# Main.net
KiCad netlist of a schematic drawn in Altium Designer
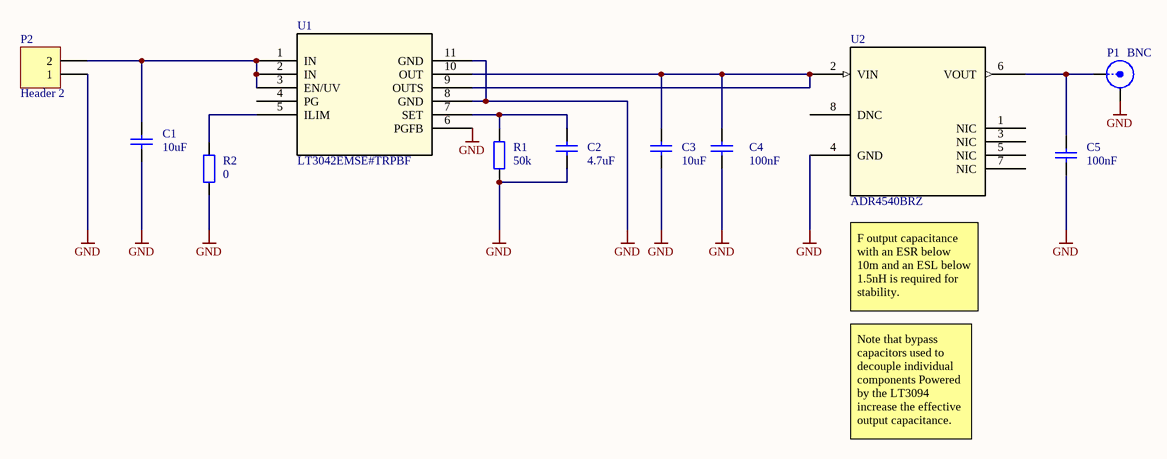
[diagram p0: Main.SchDoc]

(export (version "E")
  (design (tool "Eeschema 10.0.6"))
  (components
    (comp (ref "C1")
      (value "10uF")
      (footprint "C1206-KUE")
      (description "Capacitor")
      (fields (field (name "MANUFACTURER") "Kemet") (field (name "PUBLISHER") "Altium Limited"))
      (libsource (lib "ExtrapartsKUE_V01") (part "Capacitor"))
    )
    (comp (ref "C2")
      (value "4.7uF")
      (footprint "C1206-KUE")
      (description "Capacitor X7R")
      (fields (field (name "MANUFACTURER") "Kemet") (field (name "PUBLISHER") "Altium Limited"))
      (libsource (lib "ExtrapartsKUE_V01") (part "Capacitor"))
    )
    (comp (ref "C3")
      (value "10uF")
      (footprint "C1206-KUE")
      (description "Capacitor X7R")
      (fields (field (name "MANUFACTURER") "Kemet") (field (name "PUBLISHER") "Altium Limited"))
      (libsource (lib "ExtrapartsKUE_V01") (part "Capacitor"))
    )
    (comp (ref "C4")
      (value "100nF")
      (footprint "C1206-KUE")
      (description "Capacitor X7R")
      (fields (field (name "MANUFACTURER") "Kemet") (field (name "PUBLISHER") "Altium Limited"))
      (libsource (lib "ExtrapartsKUE_V01") (part "Capacitor"))
    )
    (comp (ref "C5")
      (value "100nF")
      (footprint "C1206-KUE")
      (description "Capacitor X7r")
      (fields (field (name "MANUFACTURER") "Kemet") (field (name "PUBLISHER") "Altium Limited"))
      (libsource (lib "ExtrapartsKUE_V01") (part "Capacitor"))
    )
    (comp (ref "P1")
      (value "BNC")
      (footprint "BNC_RA CON")
      (description "BNC Elbow Connector")
      (fields (field (name "PUBLISHER") "Altium Limited"))
      (libsource (lib "Miscellaneous Connectors") (part "BNC"))
    )
    (comp (ref "P2")
      (value "Header 2")
      (footprint "HDR1X2")
      (description "Header, 2-Pin")
      (fields (field (name "PUBLISHER") "Altium Limited"))
      (libsource (lib "Miscellaneous Connectors") (part "Header 2"))
    )
    (comp (ref "R1")
      (value "50k")
      (footprint "C1206-KUE")
      (description "Resistor SMD 1%")
      (fields (field (name "MANUFACTURER") "AVX") (field (name "PUBLISHER") "Altium Limited"))
      (libsource (lib "ExtrapartsKUE_V01") (part "ResistorSMD"))
    )
    (comp (ref "R2")
      (value "0")
      (footprint "C1206-KUE")
      (description "Resistor SMD")
      (fields (field (name "MANUFACTURER") "AVX") (field (name "PUBLISHER") "Altium Limited"))
      (libsource (lib "ExtrapartsKUE_V01") (part "ResistorSMD"))
    )
    (comp (ref "U1")
      (value "LT3042EMSE#TRPBF")
      (footprint "05-08-1664_ADI")
      (description "20V, 200mA, Ultralow Noise, Ultrahigh PSRR RF Linear Regulator")
      (fields (field (name "COPYRIGHT") "Copyright (C) 2025 Ultra Librarian. All rights reserved."))
      (libsource (lib "MyOwnParts") (part "LT3042EMSETRPBF"))
    )
    (comp (ref "U2")
      (value "ADR4540BRZ")
      (footprint "R-8_ADI")
      (description "Ultra-Low-Noise, High-Accuracy 4.096V Voltage Reference")
      (fields (field (name "COPYRIGHT") "Copyright (C) 2025 Ultra Librarian. All rights reserved."))
      (libsource (lib "ADR4540BRZ") (part "ADR4540BRZ"))
    )
  )
  (nets
    (net (code "1") (name "GND") (class "Default")
      (node (ref "C1") (pin "1") (pinfunction "1_1") (pintype "passive"))
      (node (ref "C2") (pin "1") (pinfunction "1_1") (pintype "passive"))
      (node (ref "C3") (pin "1") (pinfunction "1_1") (pintype "passive"))
      (node (ref "C4") (pin "1") (pinfunction "1_1") (pintype "passive"))
      (node (ref "C5") (pin "1") (pinfunction "1_1") (pintype "passive"))
      (node (ref "P1") (pin "2") (pinfunction "Y_2") (pintype "passive"))
      (node (ref "P2") (pin "1") (pinfunction "1_1") (pintype "passive"))
      (node (ref "R1") (pin "2") (pinfunction "2_2") (pintype "passive"))
      (node (ref "R2") (pin "2") (pinfunction "2_2") (pintype "passive"))
      (node (ref "U1") (pin "11") (pinfunction "GND_11") (pintype "power_in"))
      (node (ref "U1") (pin "6") (pinfunction "PGFB_6") (pintype "passive"))
      (node (ref "U1") (pin "8") (pinfunction "GND_8") (pintype "power_in"))
      (node (ref "U2") (pin "4") (pinfunction "GND_4") (pintype "power_in"))
    )
    (net (code "2") (name "Net-(P1-X)") (class "Default")
      (node (ref "C5") (pin "2") (pinfunction "2_2") (pintype "passive"))
      (node (ref "P1") (pin "1") (pinfunction "X_1") (pintype "passive"))
      (node (ref "U2") (pin "6") (pinfunction "VOUT_6") (pintype "output"))
    )
    (net (code "3") (name "Net-(U1-EN{slash}UV)") (class "Default")
      (node (ref "C1") (pin "2") (pinfunction "2_2") (pintype "passive"))
      (node (ref "P2") (pin "2") (pinfunction "2_2") (pintype "passive"))
      (node (ref "U1") (pin "1") (pinfunction "IN_1") (pintype "power_in"))
      (node (ref "U1") (pin "2") (pinfunction "IN_2") (pintype "power_in"))
      (node (ref "U1") (pin "3") (pinfunction "EN/UV_3") (pintype "passive"))
    )
    (net (code "4") (name "Net-(U1-ILIM)") (class "Default")
      (node (ref "R2") (pin "1") (pinfunction "1_1") (pintype "passive"))
      (node (ref "U1") (pin "5") (pinfunction "ILIM_5") (pintype "passive"))
    )
    (net (code "5") (name "Net-(U1-OUT)") (class "Default")
      (node (ref "C3") (pin "2") (pinfunction "2_2") (pintype "passive"))
      (node (ref "C4") (pin "2") (pinfunction "2_2") (pintype "passive"))
      (node (ref "U1") (pin "10") (pinfunction "OUT_10") (pintype "passive"))
      (node (ref "U1") (pin "9") (pinfunction "OUTS_9") (pintype "passive"))
      (node (ref "U2") (pin "2") (pinfunction "VIN_2") (pintype "input"))
    )
    (net (code "6") (name "Net-(U1-SET)") (class "Default")
      (node (ref "C2") (pin "2") (pinfunction "2_2") (pintype "passive"))
      (node (ref "R1") (pin "1") (pinfunction "1_1") (pintype "passive"))
      (node (ref "U1") (pin "7") (pinfunction "SET_7") (pintype "passive"))
    )
    (net (code "7") (name "unconnected-(U1-PG-Pad4)") (class "Default")
      (node (ref "U1") (pin "4") (pinfunction "PG_4") (pintype "passive"))
    )
    (net (code "8") (name "unconnected-(U2-DNC-Pad8)") (class "Default")
      (node (ref "U2") (pin "8") (pinfunction "DNC_8") (pintype "passive"))
    )
    (net (code "9") (name "unconnected-(U2-NIC-Pad1)") (class "Default")
      (node (ref "U2") (pin "1") (pinfunction "NIC_1") (pintype "passive"))
    )
    (net (code "10") (name "unconnected-(U2-NIC-Pad3)") (class "Default")
      (node (ref "U2") (pin "3") (pinfunction "NIC_3") (pintype "passive"))
    )
    (net (code "11") (name "unconnected-(U2-NIC-Pad5)") (class "Default")
      (node (ref "U2") (pin "5") (pinfunction "NIC_5") (pintype "passive"))
    )
    (net (code "12") (name "unconnected-(U2-NIC-Pad7)") (class "Default")
      (node (ref "U2") (pin "7") (pinfunction "NIC_7") (pintype "passive"))
    )
  )
)
